# Main.net
KiCad netlist of a schematic drawn in Altium Designer
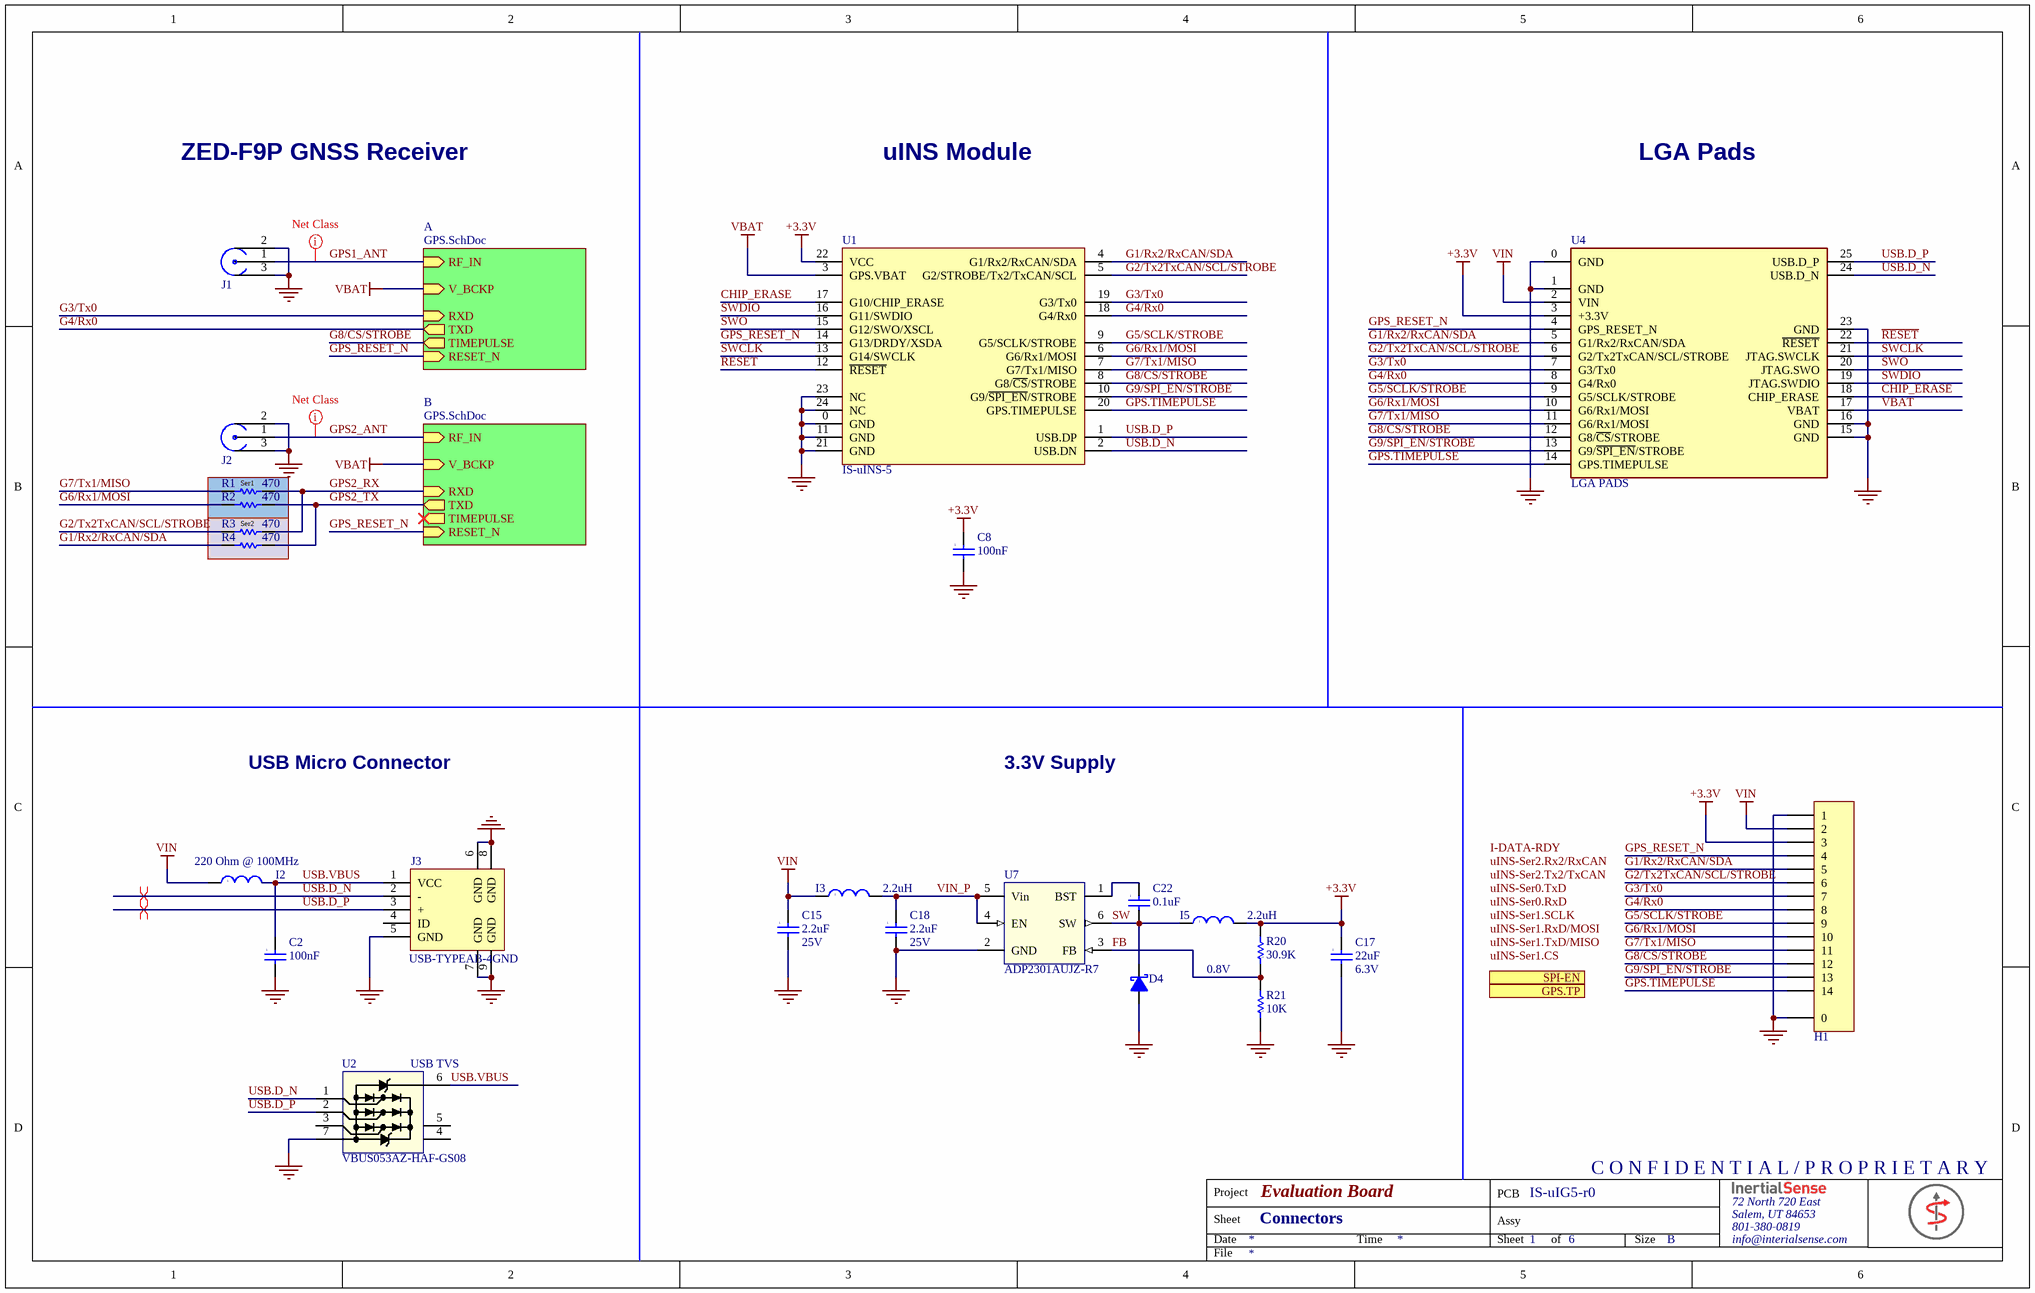
[diagram p0: Main.SchDoc]

(export (version "E")
  (design (tool "Eeschema 10.0.6"))
  (components
    (comp (ref "C2")
      (value "100nF")
      (footprint "0402")
      (description "CAP CER .10UF 50V X7R 10% 0402")
      (fields
        (field (name "MANUFACTURER") "TDK Corporation")
        (field (name "MANUFACTURER PART NUMBER") "C1005X7R1H104K")
        (field (name "PUBLISHER") "Altium Limited")
      )
      (libsource (lib "") (part "Cap_1"))
    )
    (comp (ref "C8")
      (value "100nF")
      (footprint "0402")
      (description "CAP CER .10UF 50V X7R 10% 0402")
      (fields
        (field (name "MANUFACTURER") "TDK Corporation")
        (field (name "MANUFACTURER PART NUMBER") "C1005X7R1H104K")
        (field (name "PUBLISHER") "Altium Limited")
      )
      (libsource (lib "") (part "Cap_1"))
    )
    (comp (ref "C15")
      (value "2.2uF")
      (footprint "0603")
      (description "CAP CER 2.2UF 25V X6S 0603")
      (fields
        (field (name "MANUFACTURER") "Murata")
        (field (name "MANUFACTURER PART NUMBER") "GRT188C81E225KE13D")
        (field (name "VOLTAGE RATING") "25V")
        (field (name "PUBLISHER") "Altium Limited")
      )
      (libsource (lib "General") (part "Cap"))
    )
    (comp (ref "C17")
      (value "22uF")
      (footprint "0603")
      (description "CAP CER 22UF 6.3V X6S 0603")
      (fields
        (field (name "MANUFACTURER") "Murata")
        (field (name "MANUFACTURER PART NUMBER") "GRM188C80J226ME15D")
        (field (name "VOLTAGE RATING") "6.3V")
        (field (name "PUBLISHER") "Altium Limited")
      )
      (libsource (lib "General") (part "Cap"))
    )
    (comp (ref "C18")
      (value "2.2uF")
      (footprint "0603")
      (description "CAP CER 2.2UF 25V X6S 0603")
      (fields
        (field (name "MANUFACTURER") "Murata")
        (field (name "MANUFACTURER PART NUMBER") "GRT188C81E225KE13D")
        (field (name "VOLTAGE RATING") "25V")
        (field (name "PUBLISHER") "Altium Limited")
      )
      (libsource (lib "General") (part "Cap"))
    )
    (comp (ref "C22")
      (value "0.1uF")
      (footprint "0402")
      (description "CAP CER 0.1UF 50V X7R 0402")
      (fields
        (field (name "MANUFACTURER") "TDK")
        (field (name "MANUFACTURER PART NUMBER") "CGA2B3X7R1H104K050BB")
        (field (name "PUBLISHER") "Altium Limited")
      )
      (libsource (lib "General") (part "Cap"))
    )
    (comp (ref "D4")
      (value "Diode - Schottky")
      (footprint "D0603B")
      (description "DIODE SCHOTTKY 30V 2A 0603")
      (fields
        (field (name "MANUFACTURER") "Vishay")
        (field (name "MANUFACTURER PART NUMBER") "VSKY20301608-G4-08")
      )
      (libsource (lib "General") (part "Diode - Schottky"))
    )
    (comp (ref "H1")
      (value "Hdr - 14pin - mount")
      (footprint "SM14B-GHS-TB(LF)(SN)")
      (description "Conn Shrouded Header HDR 14 POS 1.25mm Solder ST Top Entry SMD T/R")
      (fields
        (field (name "MANUFACTURER") "JST")
        (field (name "MANUFACTURER PART NUMBER") "SM14B-GHS-TB(LF)(SN)")
      )
      (libsource (lib "Connectors") (part "Hdr - 14pin - mount"))
    )
    (comp (ref "I2")
      (value "220 Ohm @ 100MHz")
      (footprint "I0603")
      (description "FERRITE CHIP 220 OHM 2500MA 0603")
      (fields
        (field (name "MANUFACTURER") "Murata Electronics North America")
        (field (name "MANUFACTURER PART NUMBER") "BLM18SG221TN1D")
      )
      (libsource (lib "") (part "Inductor_1"))
    )
    (comp (ref "I3")
      (value "2.2uH")
      (footprint "0806")
      (description "FIXED IND 2.2UH 1.2A 110 MOHM")
      (fields
        (field (name "MANUFACTURER") "TDK")
        (field (name "MANUFACTURER PART NUMBER") "MLP2016H2R2MT0S1")
      )
      (libsource (lib "General") (part "Inductor"))
    )
    (comp (ref "I5")
      (value "2.2uH")
      (footprint "0806")
      (description "FIXED IND 2.2UH 1.2A 110 MOHM")
      (fields
        (field (name "MANUFACTURER") "TDK")
        (field (name "MANUFACTURER PART NUMBER") "MLP2016H2R2MT0S1")
      )
      (libsource (lib "General") (part "Inductor"))
    )
    (comp (ref "J1")
      (value "RF - GND x 2")
      (footprint "RF UMC SMD")
      (description "CONN UMC RCPT STR 50 OHM SMD")
      (fields
        (field (name "MANUFACTURER") "Emerson Network Power Connectivity Johnson")
        (field (name "MANUFACTURER PART NUMBER") "128-0711-201")
      )
      (libsource (lib "Connectors") (part "RF - GND x 2"))
    )
    (comp (ref "J2")
      (value "RF - GND x 2")
      (footprint "RF UMC SMD")
      (description "CONN UMC RCPT STR 50 OHM SMD")
      (fields
        (field (name "MANUFACTURER") "Emerson Network Power Connectivity Johnson")
        (field (name "MANUFACTURER PART NUMBER") "128-0711-201")
      )
      (libsource (lib "Connectors") (part "RF - GND x 2"))
    )
    (comp (ref "J3")
      (value "USB-TYPEAB-4GND")
      (footprint "USB Micro AB R/A THR")
      (description "CONN USB AB 4POS")
      (fields
        (field (name "MANUFACTURER") "Amphenol FCI")
        (field (name "MANUFACTURER PART NUMBER") "10118194-0001LF")
      )
      (libsource (lib "Connectors") (part "USB-TYPEAB-4GND"))
    )
    (comp (ref "R1")
      (value "470")
      (footprint "R0402")
      (description "RES 470 OHM 1/16W 1% 0402 SMD")
      (fields
        (field (name "MANUFACTURER") "Vishay Dale")
        (field (name "MANUFACTURER PART NUMBER") "CRCW0402470RFKED")
      )
      (libsource (lib "General") (part "Res"))
    )
    (comp (ref "R2")
      (value "470")
      (footprint "R0402")
      (description "RES 470 OHM 1/16W 1% 0402 SMD")
      (fields
        (field (name "MANUFACTURER") "Vishay Dale")
        (field (name "MANUFACTURER PART NUMBER") "CRCW0402470RFKED")
      )
      (libsource (lib "General") (part "Res"))
    )
    (comp (ref "R3")
      (value "470")
      (footprint "R0402")
      (description "RES 470 OHM 1/16W 1% 0402 SMD")
      (fields
        (field (name "MANUFACTURER") "Vishay Dale")
        (field (name "MANUFACTURER PART NUMBER") "CRCW0402470RFKED")
      )
      (libsource (lib "General") (part "Res"))
    )
    (comp (ref "R4")
      (value "470")
      (footprint "R0402")
      (description "RES 470 OHM 1/16W 1% 0402 SMD")
      (fields
        (field (name "MANUFACTURER") "Vishay Dale")
        (field (name "MANUFACTURER PART NUMBER") "CRCW0402470RFKED")
      )
      (libsource (lib "General") (part "Res"))
    )
    (comp (ref "R20")
      (value "30.9K")
      (footprint "R0402")
      (description "RES TF 30.9K OHM 1% 1/16W 0402")
      (fields
        (field (name "MANUFACTURER") "Stackpole Electronics Inc")
        (field (name "MANUFACTURER PART NUMBER") "RMCF0402FT30K9")
      )
      (libsource (lib "") (part "Res_1"))
    )
    (comp (ref "R21")
      (value "10K")
      (footprint "R0402")
      (description "RES 10.0K OHM 1/16W 1% 0402 SMD")
      (fields
        (field (name "MANUFACTURER") "Yageo")
        (field (name "MANUFACTURER PART NUMBER") "RC0402FR-0710KL")
      )
      (libsource (lib "") (part "Res_1"))
    )
    (comp (ref "U1")
      (value "uINS")
      (footprint "IS-uINS-5.0")
      (description "Inertial Sense uINS")
      (fields
        (field (name "MANUFACTURER") "Inertial Sense")
        (field (name "MANUFACTURER PART NUMBER") "IS-uINS-5")
      )
      (libsource (lib "IS-uINS-5") (part "IS-uINS-5.0"))
    )
    (comp (ref "U2")
      (value "VBUS053")
      (footprint "QFN50P160X160X60-6N")
      (description "ESD SUPPRESS 5.5V 36W 3-Line USB")
      (fields
        (field (name "MANUFACTURER") "Vishay Semiconductors")
        (field (name "MANUFACTURER PART NUMBER") "VBUS053AZ-HAF-GS08")
      )
      (libsource (lib "ICs") (part "VBUS053"))
    )
    (comp (ref "U4")
      (value "LGA PADS")
      (footprint "uIG5p1_LGA")
      (description "Inertial Sense uIG5 GNSS INS Module")
      (libsource (lib "Sensors") (part "uIG5p0_LGA"))
    )
    (comp (ref "U7")
      (value "ADP2301")
      (footprint "MO-178-AB")
      (description "IC BUCK ADJ 1.2A 6TSOT")
      (fields
        (field (name "MANUFACTURER") "Analog Devices Inc")
        (field (name "MANUFACTURER PART NUMBER") "ADP2301AUJZ-R7")
      )
      (libsource (lib "ICs") (part "ADP2301"))
    )
  )
  (nets
    (net (code "1") (name "+3.3V") (class "Default")
      (node (ref "C17") (pin "1") (pinfunction "1_1") (pintype "passive"))
      (node (ref "C8") (pin "1") (pinfunction "1_1") (pintype "passive"))
      (node (ref "H1") (pin "3") (pinfunction "3_3") (pintype "passive"))
      (node (ref "I5") (pin "2") (pinfunction "2_2") (pintype "passive"))
      (node (ref "R20") (pin "2") (pinfunction "2_2") (pintype "passive"))
      (node (ref "U1") (pin "22") (pinfunction "VCC_22") (pintype "power_in"))
      (node (ref "U4") (pin "3") (pinfunction "+3.3V_3") (pintype "passive"))
    )
    (net (code "2") (name "/CHIP_ERASE") (class "Default")
      (node (ref "U1") (pin "17") (pinfunction "G10/CHIP_ERASE_17") (pintype "passive"))
      (node (ref "U4") (pin "18") (pinfunction "CHIP_ERASE_18") (pintype "passive"))
    )
    (net (code "3") (name "/FB") (class "Default")
      (node (ref "R20") (pin "1") (pinfunction "1_1") (pintype "passive"))
      (node (ref "R21") (pin "2") (pinfunction "2_2") (pintype "passive"))
      (node (ref "U7") (pin "3") (pinfunction "FB_3") (pintype "input"))
    )
    (net (code "4") (name "/G1{slash}Rx2{slash}RxCAN{slash}SDA") (class "Default")
      (node (ref "H1") (pin "5") (pinfunction "5_5") (pintype "passive"))
      (node (ref "R4") (pin "1") (pinfunction "1_1") (pintype "passive"))
      (node (ref "U1") (pin "4") (pinfunction "G1/Rx2/RxCAN/SDA_4") (pintype "passive"))
      (node (ref "U4") (pin "5") (pinfunction "G1/Rx2/RxCAN/SDA_5") (pintype "passive"))
    )
    (net (code "5") (name "/G2{slash}Tx2TxCAN{slash}SCL{slash}STROBE") (class "Default")
      (node (ref "H1") (pin "6") (pinfunction "6_6") (pintype "passive"))
      (node (ref "R3") (pin "1") (pinfunction "1_1") (pintype "passive"))
      (node (ref "U1") (pin "5") (pinfunction "G2/STROBE/Tx2/TxCAN/SCL_5") (pintype "passive"))
      (node (ref "U4") (pin "6") (pinfunction "G2/Tx2TxCAN/SCL/STROBE_6") (pintype "passive"))
    )
    (net (code "6") (name "/G3{slash}Tx0") (class "Default")
      (node (ref "H1") (pin "7") (pinfunction "7_7") (pintype "passive"))
      (node (ref "U1") (pin "19") (pinfunction "G3/Tx0_19") (pintype "passive"))
      (node (ref "U4") (pin "7") (pinfunction "G3/Tx0_7") (pintype "passive"))
    )
    (net (code "7") (name "/G4{slash}Rx0") (class "Default")
      (node (ref "H1") (pin "8") (pinfunction "8_8") (pintype "passive"))
      (node (ref "U1") (pin "18") (pinfunction "G4/Rx0_18") (pintype "passive"))
      (node (ref "U4") (pin "8") (pinfunction "G4/Rx0_8") (pintype "passive"))
    )
    (net (code "8") (name "/G5{slash}SCLK{slash}STROBE") (class "Default")
      (node (ref "H1") (pin "9") (pinfunction "9_9") (pintype "passive"))
      (node (ref "U1") (pin "9") (pinfunction "G5/SCLK/STROBE_9") (pintype "passive"))
      (node (ref "U4") (pin "9") (pinfunction "G5/SCLK/STROBE_9") (pintype "passive"))
    )
    (net (code "9") (name "/G6{slash}Rx1{slash}MOSI") (class "Default")
      (node (ref "H1") (pin "10") (pinfunction "10_10") (pintype "passive"))
      (node (ref "R2") (pin "1") (pinfunction "1_1") (pintype "passive"))
      (node (ref "U1") (pin "6") (pinfunction "G6/Rx1/MOSI_6") (pintype "passive"))
      (node (ref "U4") (pin "10") (pinfunction "G6/Rx1/MOSI_10") (pintype "passive"))
    )
    (net (code "10") (name "/G7{slash}Tx1{slash}MISO") (class "Default")
      (node (ref "H1") (pin "11") (pinfunction "11_11") (pintype "passive"))
      (node (ref "R1") (pin "1") (pinfunction "1_1") (pintype "passive"))
      (node (ref "U1") (pin "7") (pinfunction "G7/Tx1/MISO_7") (pintype "passive"))
      (node (ref "U4") (pin "11") (pinfunction "G6/Rx1/MOSI_11") (pintype "passive"))
    )
    (net (code "11") (name "/G8{slash}~{CS}{slash}STROBE") (class "Default")
      (node (ref "H1") (pin "12") (pinfunction "12_12") (pintype "passive"))
      (node (ref "U1") (pin "8") (pinfunction "G8/~{CS}/STROBE_8") (pintype "passive"))
      (node (ref "U4") (pin "12") (pinfunction "G8/~{CS}/STROBE_12") (pintype "passive"))
    )
    (net (code "12") (name "/G9{slash}~{SPI_EN}{slash}STROBE") (class "Default")
      (node (ref "H1") (pin "13") (pinfunction "13_13") (pintype "passive"))
      (node (ref "U1") (pin "10") (pinfunction "G9/~{SPI_EN}/STROBE_10") (pintype "passive"))
      (node (ref "U4") (pin "13") (pinfunction "G9/~{SPI_EN}/STROBE_13") (pintype "passive"))
    )
    (net (code "13") (name "/GPS.TIMEPULSE") (class "Default")
      (node (ref "H1") (pin "14") (pinfunction "14_14") (pintype "passive"))
      (node (ref "U1") (pin "20") (pinfunction "GPS.TIMEPULSE_20") (pintype "passive"))
      (node (ref "U4") (pin "14") (pinfunction "GPS.TIMEPULSE_14") (pintype "passive"))
    )
    (net (code "15") (name "/GPS1_ANT") (class "Default")
      (node (ref "J1") (pin "1") (pinfunction "1_1") (pintype "passive"))
    )
    (net (code "16") (name "/GPS2_ANT") (class "Default")
      (node (ref "J2") (pin "1") (pinfunction "1_1") (pintype "passive"))
    )
    (net (code "17") (name "/GPS2_RX") (class "Default")
      (node (ref "R1") (pin "2") (pinfunction "2_2") (pintype "passive"))
      (node (ref "R3") (pin "2") (pinfunction "2_2") (pintype "passive"))
    )
    (net (code "18") (name "/GPS2_TX") (class "Default")
      (node (ref "R2") (pin "2") (pinfunction "2_2") (pintype "passive"))
      (node (ref "R4") (pin "2") (pinfunction "2_2") (pintype "passive"))
    )
    (net (code "19") (name "/GPS_RESET_N") (class "Default")
      (node (ref "H1") (pin "4") (pinfunction "4_4") (pintype "passive"))
      (node (ref "U1") (pin "14") (pinfunction "G13/DRDY/XSDA_14") (pintype "passive"))
      (node (ref "U4") (pin "4") (pinfunction "GPS_RESET_N_4") (pintype "passive"))
    )
    (net (code "21") (name "/RESET") (class "Default")
      (node (ref "U1") (pin "12") (pinfunction "~{RESET}_12") (pintype "passive"))
      (node (ref "U4") (pin "22") (pinfunction "~{RESET}_22") (pintype "passive"))
    )
    (net (code "23") (name "/SW") (class "Default")
      (node (ref "C22") (pin "2") (pinfunction "2_2") (pintype "passive"))
      (node (ref "D4") (pin "C") (pinfunction "C_C") (pintype "passive"))
      (node (ref "I5") (pin "1") (pinfunction "1_1") (pintype "passive"))
      (node (ref "U7") (pin "6") (pinfunction "SW_6") (pintype "output"))
    )
    (net (code "24") (name "/SWCLK") (class "Default")
      (node (ref "U1") (pin "13") (pinfunction "G14/SWCLK_13") (pintype "passive"))
      (node (ref "U4") (pin "21") (pinfunction "JTAG.SWCLK_21") (pintype "passive"))
    )
    (net (code "25") (name "/SWDIO") (class "Default")
      (node (ref "U1") (pin "16") (pinfunction "G11/SWDIO_16") (pintype "passive"))
      (node (ref "U4") (pin "19") (pinfunction "JTAG.SWDIO_19") (pintype "passive"))
    )
    (net (code "26") (name "/SWO") (class "Default")
      (node (ref "U1") (pin "15") (pinfunction "G12/SWO/XSCL_15") (pintype "passive"))
      (node (ref "U4") (pin "20") (pinfunction "JTAG.SWO_20") (pintype "passive"))
    )
    (net (code "28") (name "/USB.D_N") (class "Default")
      (node (ref "J3") (pin "2") (pinfunction "-_2") (pintype "passive"))
      (node (ref "U1") (pin "2") (pinfunction "USB.DN_2") (pintype "passive"))
      (node (ref "U2") (pin "1") (pintype "passive"))
      (node (ref "U4") (pin "24") (pinfunction "USB.D_N_24") (pintype "passive"))
    )
    (net (code "29") (name "/USB.D_P") (class "Default")
      (node (ref "J3") (pin "3") (pinfunction "+_3") (pintype "passive"))
      (node (ref "U1") (pin "1") (pinfunction "USB.DP_1") (pintype "passive"))
      (node (ref "U2") (pin "2") (pintype "passive"))
      (node (ref "U4") (pin "25") (pinfunction "USB.D_P_25") (pintype "passive"))
    )
    (net (code "30") (name "/USB.VBUS") (class "Default")
      (node (ref "C2") (pin "1") (pinfunction "1_1") (pintype "passive"))
      (node (ref "I2") (pin "2") (pinfunction "2_2") (pintype "passive"))
      (node (ref "J3") (pin "1") (pinfunction "VCC_1") (pintype "passive"))
      (node (ref "U2") (pin "6") (pintype "passive"))
    )
    (net (code "31") (name "/VIN_P") (class "Default")
      (node (ref "C18") (pin "1") (pinfunction "1_1") (pintype "passive"))
      (node (ref "I3") (pin "2") (pinfunction "2_2") (pintype "passive"))
      (node (ref "U7") (pin "4") (pinfunction "EN_4") (pintype "input"))
      (node (ref "U7") (pin "5") (pinfunction "Vin_5") (pintype "power_in"))
    )
    (net (code "40") (name "GND") (class "Default")
      (node (ref "C15") (pin "2") (pinfunction "2_2") (pintype "passive"))
      (node (ref "C17") (pin "2") (pinfunction "2_2") (pintype "passive"))
      (node (ref "C18") (pin "2") (pinfunction "2_2") (pintype "passive"))
      (node (ref "C2") (pin "2") (pinfunction "2_2") (pintype "passive"))
      (node (ref "C8") (pin "2") (pinfunction "2_2") (pintype "passive"))
      (node (ref "D4") (pin "A") (pinfunction "A_A") (pintype "passive"))
      (node (ref "H1") (pin "0") (pinfunction "0_0") (pintype "passive"))
      (node (ref "H1") (pin "1") (pinfunction "1_1") (pintype "passive"))
      (node (ref "J1") (pin "2") (pinfunction "2_2") (pintype "passive"))
      (node (ref "J1") (pin "3") (pinfunction "3_3") (pintype "passive"))
      (node (ref "J2") (pin "2") (pinfunction "2_2") (pintype "passive"))
      (node (ref "J2") (pin "3") (pinfunction "3_3") (pintype "passive"))
      (node (ref "J3") (pin "5") (pinfunction "GND_5") (pintype "passive"))
      (node (ref "J3") (pin "6") (pinfunction "GND_6") (pintype "passive"))
      (node (ref "J3") (pin "7") (pinfunction "GND_7") (pintype "passive"))
      (node (ref "J3") (pin "8") (pinfunction "GND_8") (pintype "passive"))
      (node (ref "J3") (pin "9") (pinfunction "GND_9") (pintype "passive"))
      (node (ref "R21") (pin "1") (pinfunction "1_1") (pintype "passive"))
      (node (ref "U1") (pin "0") (pinfunction "GND_0") (pintype "power_in"))
      (node (ref "U1") (pin "11") (pinfunction "GND_11") (pintype "power_in"))
      (node (ref "U1") (pin "21") (pinfunction "GND_21") (pintype "power_in"))
      (node (ref "U1") (pin "23") (pinfunction "NC_23") (pintype "power_in"))
      (node (ref "U1") (pin "24") (pinfunction "NC_24") (pintype "power_in"))
      (node (ref "U2") (pin "7") (pintype "passive"))
      (node (ref "U4") (pin "0") (pinfunction "GND_0") (pintype "passive"))
      (node (ref "U4") (pin "1") (pinfunction "GND_1") (pintype "passive"))
      (node (ref "U4") (pin "15") (pinfunction "GND_15") (pintype "passive"))
      (node (ref "U4") (pin "16") (pinfunction "GND_16") (pintype "passive"))
      (node (ref "U4") (pin "23") (pinfunction "GND_23") (pintype "passive"))
      (node (ref "U7") (pin "2") (pinfunction "GND_2") (pintype "power_in"))
    )
    (net (code "41") (name "Net-(U7-BST)") (class "Default")
      (node (ref "C22") (pin "1") (pinfunction "1_1") (pintype "passive"))
      (node (ref "U7") (pin "1") (pinfunction "BST_1") (pintype "passive"))
    )
    (net (code "42") (name "VBAT") (class "Default")
      (node (ref "U1") (pin "3") (pinfunction "GPS.VBAT_3") (pintype "passive"))
      (node (ref "U4") (pin "17") (pinfunction "VBAT_17") (pintype "passive"))
    )
    (net (code "43") (name "VIN") (class "Default")
      (node (ref "C15") (pin "1") (pinfunction "1_1") (pintype "passive"))
      (node (ref "H1") (pin "2") (pinfunction "2_2") (pintype "passive"))
      (node (ref "I2") (pin "1") (pinfunction "1_1") (pintype "passive"))
      (node (ref "I3") (pin "1") (pinfunction "1_1") (pintype "passive"))
      (node (ref "U4") (pin "2") (pinfunction "VIN_2") (pintype "passive"))
    )
    (net (code "44") (name "unconnected-(J3-ID-Pad4)") (class "Default")
      (node (ref "J3") (pin "4") (pinfunction "ID_4") (pintype "passive"))
    )
    (net (code "45") (name "unconnected-(U2-Pad3)") (class "Default")
      (node (ref "U2") (pin "3") (pintype "passive"))
    )
    (net (code "46") (name "unconnected-(U2-nc-Pad4)") (class "Default")
      (node (ref "U2") (pin "4") (pinfunction "nc_4") (pintype "passive"))
    )
    (net (code "47") (name "unconnected-(U2-nc-Pad5)") (class "Default")
      (node (ref "U2") (pin "5") (pinfunction "nc_5") (pintype "passive"))
    )
  )
)
